# PCM1803A_Breakout-v11.net
KiCad netlist of a schematic drawn in EAGLE
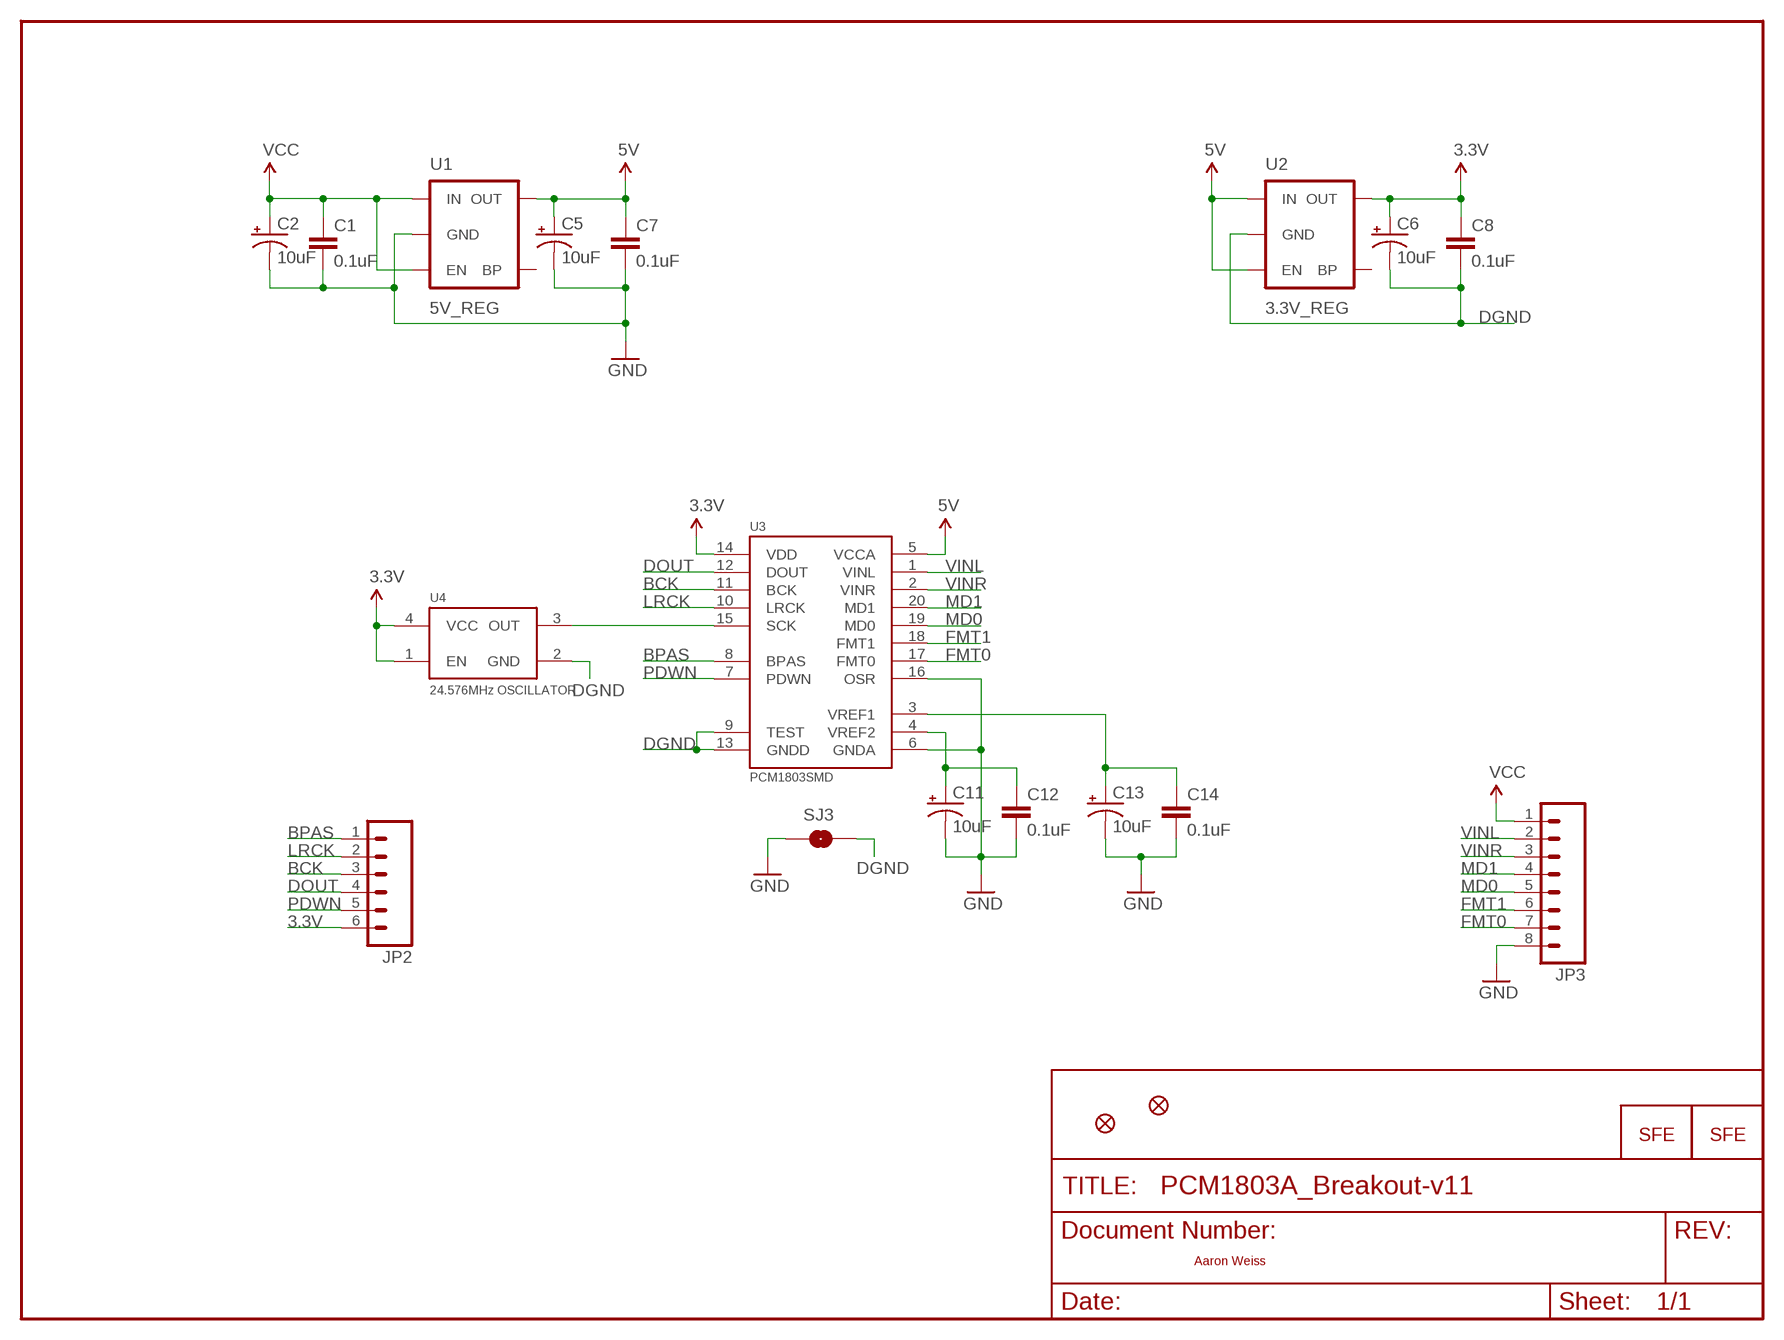
[diagram p0: schematic, sheet 1]

(export (version "E")
  (design (tool "Eeschema 10.0.6"))
  (components
    (comp (ref "C1")
      (value "0.1uF")
      (footprint "eagle-import:0402-CAP")
      (libsource (lib "eagle-import") (part "CAP0402-CAP"))
    )
    (comp (ref "C2")
      (value "10uF")
      (footprint "eagle-import:EIA3216")
      (libsource (lib "eagle-import") (part "CAP_POL1206"))
    )
    (comp (ref "C5")
      (value "10uF")
      (footprint "eagle-import:EIA3216")
      (libsource (lib "eagle-import") (part "CAP_POL1206"))
    )
    (comp (ref "C6")
      (value "10uF")
      (footprint "eagle-import:EIA3216")
      (libsource (lib "eagle-import") (part "CAP_POL1206"))
    )
    (comp (ref "C7")
      (value "0.1uF")
      (footprint "eagle-import:0402-CAP")
      (libsource (lib "eagle-import") (part "CAP0402-CAP"))
    )
    (comp (ref "C8")
      (value "0.1uF")
      (footprint "eagle-import:0402-CAP")
      (libsource (lib "eagle-import") (part "CAP0402-CAP"))
    )
    (comp (ref "C11")
      (value "10uF")
      (footprint "eagle-import:EIA3216")
      (libsource (lib "eagle-import") (part "CAP_POL1206"))
    )
    (comp (ref "C12")
      (value "0.1uF")
      (footprint "eagle-import:0402-CAP")
      (libsource (lib "eagle-import") (part "CAP0402-CAP"))
    )
    (comp (ref "C13")
      (value "10uF")
      (footprint "eagle-import:EIA3216")
      (libsource (lib "eagle-import") (part "CAP_POL1206"))
    )
    (comp (ref "C14")
      (value "0.1uF")
      (footprint "eagle-import:0402-CAP")
      (libsource (lib "eagle-import") (part "CAP0402-CAP"))
    )
    (comp (ref "JP1")
      (value "LOGO-SFESK")
      (footprint "eagle-import:SFE-LOGO-FLAME")
      (libsource (lib "eagle-import") (part "LOGO-SFESK"))
    )
    (comp (ref "JP2")
      (value "M06SIP")
      (footprint "eagle-import:1X06")
      (libsource (lib "eagle-import") (part "M06SIP"))
    )
    (comp (ref "JP3")
      (value "M08")
      (footprint "eagle-import:1X08")
      (libsource (lib "eagle-import") (part "M08"))
    )
    (comp (ref "JP4")
      (value "FIDUCIAL1X2")
      (footprint "eagle-import:FIDUCIAL-1X2")
      (libsource (lib "eagle-import") (part "FIDUCIAL1X2"))
    )
    (comp (ref "JP5")
      (value "FIDUCIAL1X2")
      (footprint "eagle-import:FIDUCIAL-1X2")
      (libsource (lib "eagle-import") (part "FIDUCIAL1X2"))
    )
    (comp (ref "SJ3")
      (value "SOLDERJUMPERTRACE")
      (footprint "eagle-import:SJ_2S-TRACE")
      (libsource (lib "eagle-import") (part "SOLDERJUMPERTRACE"))
    )
    (comp (ref "U$4")
      (value "LOGO-SFENEW")
      (footprint "eagle-import:SFE-NEW-WEBLOGO")
      (libsource (lib "eagle-import") (part "LOGO-SFENEW"))
    )
    (comp (ref "U1")
      (value "5V_REG")
      (footprint "eagle-import:SOT23-5")
      (libsource (lib "eagle-import") (part "V_REG_LDOSMD"))
    )
    (comp (ref "U2")
      (value "3.3V_REG")
      (footprint "eagle-import:SOT23-5")
      (libsource (lib "eagle-import") (part "V_REG_LDOSMD"))
    )
    (comp (ref "U3")
      (value "PCM1803SMD")
      (footprint "eagle-import:SSOP20")
      (libsource (lib "eagle-import") (part "PCM1803SMD"))
    )
    (comp (ref "U4")
      (value "24.576MHz OSCILLATOR")
      (footprint "eagle-import:CRYSTAL-SMD-7.5X5.2-6PIN")
      (libsource (lib "eagle-import") (part "OSCILLATORSMD6"))
    )
  )
  (nets
    (net (code "1") (name "/BCK") (class "Default")
      (node (ref "JP2") (pin "3") (pinfunction "3_3") (pintype "passive"))
      (node (ref "U3") (pin "11") (pinfunction "BCK_11") (pintype "bidirectional"))
    )
    (net (code "2") (name "/BPAS") (class "Default")
      (node (ref "JP2") (pin "1") (pinfunction "1_1") (pintype "passive"))
      (node (ref "U3") (pin "8") (pinfunction "BPAS_8") (pintype "bidirectional"))
    )
    (net (code "3") (name "/DGND") (class "Default")
      (node (ref "C6") (pin "C") (pinfunction "-_C") (pintype "passive"))
      (node (ref "C8") (pin "2") (pinfunction "2_2") (pintype "passive"))
      (node (ref "SJ3") (pin "2") (pinfunction "2_2") (pintype "passive"))
      (node (ref "U2") (pin "2") (pinfunction "GND_2") (pintype "input"))
      (node (ref "U3") (pin "13") (pinfunction "GNDD_13") (pintype "bidirectional"))
      (node (ref "U3") (pin "9") (pinfunction "TEST_9") (pintype "bidirectional"))
      (node (ref "U4") (pin "2") (pinfunction "GND_2") (pintype "bidirectional"))
    )
    (net (code "4") (name "/DOUT") (class "Default")
      (node (ref "JP2") (pin "4") (pinfunction "4_4") (pintype "passive"))
      (node (ref "U3") (pin "12") (pinfunction "DOUT_12") (pintype "bidirectional"))
    )
    (net (code "5") (name "/FMT0") (class "Default")
      (node (ref "JP3") (pin "7") (pinfunction "7_7") (pintype "passive"))
      (node (ref "U3") (pin "17") (pinfunction "FMT0_17") (pintype "bidirectional"))
    )
    (net (code "6") (name "/FMT1") (class "Default")
      (node (ref "JP3") (pin "6") (pinfunction "6_6") (pintype "passive"))
      (node (ref "U3") (pin "18") (pinfunction "FMT1_18") (pintype "bidirectional"))
    )
    (net (code "7") (name "/LRCK") (class "Default")
      (node (ref "JP2") (pin "2") (pinfunction "2_2") (pintype "passive"))
      (node (ref "U3") (pin "10") (pinfunction "LRCK_10") (pintype "bidirectional"))
    )
    (net (code "8") (name "/MD0") (class "Default")
      (node (ref "JP3") (pin "5") (pinfunction "5_5") (pintype "passive"))
      (node (ref "U3") (pin "19") (pinfunction "MD0_19") (pintype "bidirectional"))
    )
    (net (code "9") (name "/MD1") (class "Default")
      (node (ref "JP3") (pin "4") (pinfunction "4_4") (pintype "passive"))
      (node (ref "U3") (pin "20") (pinfunction "MD1_20") (pintype "bidirectional"))
    )
    (net (code "10") (name "/PDWN") (class "Default")
      (node (ref "JP2") (pin "5") (pinfunction "5_5") (pintype "passive"))
      (node (ref "U3") (pin "7") (pinfunction "PDWN_7") (pintype "bidirectional"))
    )
    (net (code "11") (name "/VINL") (class "Default")
      (node (ref "JP3") (pin "2") (pinfunction "2_2") (pintype "passive"))
      (node (ref "U3") (pin "1") (pinfunction "VINL_1") (pintype "bidirectional"))
    )
    (net (code "12") (name "/VINR") (class "Default")
      (node (ref "JP3") (pin "3") (pinfunction "3_3") (pintype "passive"))
      (node (ref "U3") (pin "2") (pinfunction "VINR_2") (pintype "bidirectional"))
    )
    (net (code "13") (name "3.3V") (class "Default")
      (node (ref "C6") (pin "A") (pinfunction "+_A") (pintype "passive"))
      (node (ref "C8") (pin "1") (pinfunction "1_1") (pintype "passive"))
      (node (ref "JP2") (pin "6") (pinfunction "6_6") (pintype "passive"))
      (node (ref "U2") (pin "5") (pinfunction "OUT_5") (pintype "passive"))
      (node (ref "U3") (pin "14") (pinfunction "VDD_14") (pintype "bidirectional"))
      (node (ref "U4") (pin "1") (pinfunction "EN_1") (pintype "bidirectional"))
      (node (ref "U4") (pin "4") (pinfunction "VCC_4") (pintype "bidirectional"))
    )
    (net (code "14") (name "5V") (class "Default")
      (node (ref "C5") (pin "A") (pinfunction "+_A") (pintype "passive"))
      (node (ref "C7") (pin "1") (pinfunction "1_1") (pintype "passive"))
      (node (ref "U1") (pin "5") (pinfunction "OUT_5") (pintype "passive"))
      (node (ref "U2") (pin "1") (pinfunction "IN_1") (pintype "input"))
      (node (ref "U2") (pin "3") (pinfunction "EN_3") (pintype "input"))
      (node (ref "U3") (pin "5") (pinfunction "VCCA_5") (pintype "bidirectional"))
    )
    (net (code "15") (name "GND") (class "Default")
      (node (ref "C1") (pin "2") (pinfunction "2_2") (pintype "passive"))
      (node (ref "C11") (pin "C") (pinfunction "-_C") (pintype "passive"))
      (node (ref "C12") (pin "2") (pinfunction "2_2") (pintype "passive"))
      (node (ref "C13") (pin "C") (pinfunction "-_C") (pintype "passive"))
      (node (ref "C14") (pin "2") (pinfunction "2_2") (pintype "passive"))
      (node (ref "C2") (pin "C") (pinfunction "-_C") (pintype "passive"))
      (node (ref "C5") (pin "C") (pinfunction "-_C") (pintype "passive"))
      (node (ref "C7") (pin "2") (pinfunction "2_2") (pintype "passive"))
      (node (ref "JP3") (pin "8") (pinfunction "8_8") (pintype "passive"))
      (node (ref "SJ3") (pin "1") (pinfunction "1_1") (pintype "passive"))
      (node (ref "U1") (pin "2") (pinfunction "GND_2") (pintype "input"))
      (node (ref "U3") (pin "16") (pinfunction "OSR_16") (pintype "bidirectional"))
      (node (ref "U3") (pin "6") (pinfunction "GNDA_6") (pintype "bidirectional"))
    )
    (net (code "16") (name "Net-(C11-+)") (class "Default")
      (node (ref "C11") (pin "A") (pinfunction "+_A") (pintype "passive"))
      (node (ref "C12") (pin "1") (pinfunction "1_1") (pintype "passive"))
      (node (ref "U3") (pin "4") (pinfunction "VREF2_4") (pintype "bidirectional"))
    )
    (net (code "17") (name "Net-(C13-+)") (class "Default")
      (node (ref "C13") (pin "A") (pinfunction "+_A") (pintype "passive"))
      (node (ref "C14") (pin "1") (pinfunction "1_1") (pintype "passive"))
      (node (ref "U3") (pin "3") (pinfunction "VREF1_3") (pintype "bidirectional"))
    )
    (net (code "18") (name "Net-(U3-SCK)") (class "Default")
      (node (ref "U3") (pin "15") (pinfunction "SCK_15") (pintype "bidirectional"))
      (node (ref "U4") (pin "3") (pinfunction "OUT_3") (pintype "bidirectional"))
    )
    (net (code "19") (name "VCC") (class "Default")
      (node (ref "C1") (pin "1") (pinfunction "1_1") (pintype "passive"))
      (node (ref "C2") (pin "A") (pinfunction "+_A") (pintype "passive"))
      (node (ref "JP3") (pin "1") (pinfunction "1_1") (pintype "passive"))
      (node (ref "U1") (pin "1") (pinfunction "IN_1") (pintype "input"))
      (node (ref "U1") (pin "3") (pinfunction "EN_3") (pintype "input"))
    )
    (net (code "20") (name "unconnected-(U1-BP-Pad4)") (class "Default")
      (node (ref "U1") (pin "4") (pinfunction "BP_4") (pintype "input"))
    )
    (net (code "21") (name "unconnected-(U2-BP-Pad4)") (class "Default")
      (node (ref "U2") (pin "4") (pinfunction "BP_4") (pintype "input"))
    )
  )
)
